# 1.net
KiCad netlist of a schematic drawn in Altium Designer
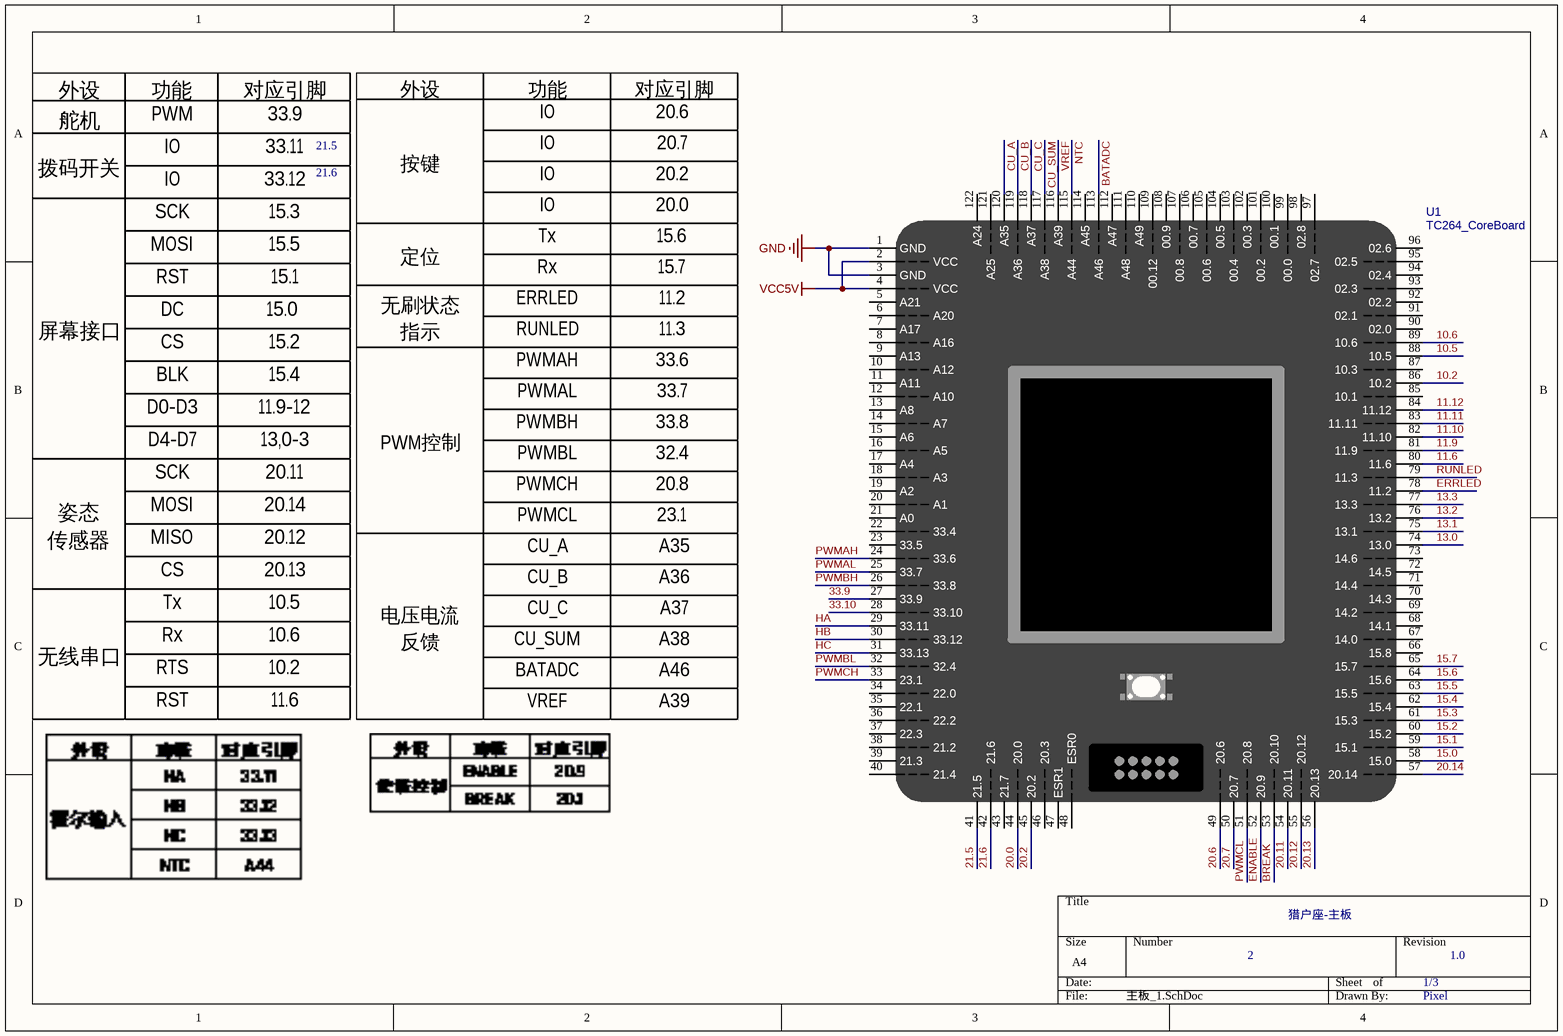
[diagram p0: 主板_1.SchDoc]

(export (version "E")
  (design (tool "Eeschema 10.0.6"))
  (components
    (comp (ref "U1")
      (value "TC264_CoreBoard")
      (footprint "TC264_CoreBoard")
      (description "逐飞科技TC264核心板")
      (libsource (lib "TC264_主板_V2.6") (part "TC264_CoreBoard"))
    )
  )
  (nets
    (net (code "1") (name "/10.2") (class "Default")
      (node (ref "U1") (pin "86") (pinfunction "10.2_86") (pintype "passive"))
    )
    (net (code "2") (name "/10.5") (class "Default")
      (node (ref "U1") (pin "88") (pinfunction "10.5_88") (pintype "passive"))
    )
    (net (code "3") (name "/10.6") (class "Default")
      (node (ref "U1") (pin "89") (pinfunction "10.6_89") (pintype "passive"))
    )
    (net (code "4") (name "/11.6") (class "Default")
      (node (ref "U1") (pin "80") (pinfunction "11.6_80") (pintype "passive"))
    )
    (net (code "5") (name "/11.9") (class "Default")
      (node (ref "U1") (pin "81") (pinfunction "11.9_81") (pintype "passive"))
    )
    (net (code "6") (name "/11.10") (class "Default")
      (node (ref "U1") (pin "82") (pinfunction "11.10_82") (pintype "passive"))
    )
    (net (code "7") (name "/11.11") (class "Default")
      (node (ref "U1") (pin "83") (pinfunction "11.11_83") (pintype "passive"))
    )
    (net (code "8") (name "/11.12") (class "Default")
      (node (ref "U1") (pin "84") (pinfunction "11.12_84") (pintype "passive"))
    )
    (net (code "9") (name "/13.0") (class "Default")
      (node (ref "U1") (pin "74") (pinfunction "13.0_74") (pintype "passive"))
    )
    (net (code "10") (name "/13.1") (class "Default")
      (node (ref "U1") (pin "75") (pinfunction "13.1_75") (pintype "passive"))
    )
    (net (code "11") (name "/13.2") (class "Default")
      (node (ref "U1") (pin "76") (pinfunction "13.2_76") (pintype "passive"))
    )
    (net (code "12") (name "/13.3") (class "Default")
      (node (ref "U1") (pin "77") (pinfunction "13.3_77") (pintype "passive"))
    )
    (net (code "13") (name "/15.0") (class "Default")
      (node (ref "U1") (pin "58") (pinfunction "15.0_58") (pintype "passive"))
    )
    (net (code "14") (name "/15.1") (class "Default")
      (node (ref "U1") (pin "59") (pinfunction "15.1_59") (pintype "passive"))
    )
    (net (code "15") (name "/15.2") (class "Default")
      (node (ref "U1") (pin "60") (pinfunction "15.2_60") (pintype "passive"))
    )
    (net (code "16") (name "/15.3") (class "Default")
      (node (ref "U1") (pin "61") (pinfunction "15.3_61") (pintype "passive"))
    )
    (net (code "17") (name "/15.4") (class "Default")
      (node (ref "U1") (pin "62") (pinfunction "15.4_62") (pintype "passive"))
    )
    (net (code "18") (name "/15.5") (class "Default")
      (node (ref "U1") (pin "63") (pinfunction "15.5_63") (pintype "passive"))
    )
    (net (code "19") (name "/15.6") (class "Default")
      (node (ref "U1") (pin "64") (pinfunction "15.6_64") (pintype "passive"))
    )
    (net (code "20") (name "/15.7") (class "Default")
      (node (ref "U1") (pin "65") (pinfunction "15.7_65") (pintype "passive"))
    )
    (net (code "21") (name "/20.0") (class "Default")
      (node (ref "U1") (pin "44") (pinfunction "20.0_44") (pintype "passive"))
    )
    (net (code "22") (name "/20.2") (class "Default")
      (node (ref "U1") (pin "45") (pinfunction "20.2_45") (pintype "passive"))
    )
    (net (code "23") (name "/20.6") (class "Default")
      (node (ref "U1") (pin "49") (pinfunction "20.6_49") (pintype "passive"))
    )
    (net (code "24") (name "/20.7") (class "Default")
      (node (ref "U1") (pin "50") (pinfunction "20.7_50") (pintype "passive"))
    )
    (net (code "25") (name "/20.11") (class "Default")
      (node (ref "U1") (pin "54") (pinfunction "20.11_54") (pintype "passive"))
    )
    (net (code "26") (name "/20.12") (class "Default")
      (node (ref "U1") (pin "55") (pinfunction "20.12_55") (pintype "passive"))
    )
    (net (code "27") (name "/20.13") (class "Default")
      (node (ref "U1") (pin "56") (pinfunction "20.13_56") (pintype "passive"))
    )
    (net (code "28") (name "/20.14") (class "Default")
      (node (ref "U1") (pin "57") (pinfunction "20.14_57") (pintype "passive"))
    )
    (net (code "29") (name "/21.5") (class "Default")
      (node (ref "U1") (pin "41") (pinfunction "21.5_41") (pintype "passive"))
    )
    (net (code "30") (name "/21.6") (class "Default")
      (node (ref "U1") (pin "42") (pinfunction "21.6_42") (pintype "passive"))
    )
    (net (code "31") (name "/33.9") (class "Default")
      (node (ref "U1") (pin "27") (pinfunction "33.9_27") (pintype "passive"))
    )
    (net (code "32") (name "/33.10") (class "Default")
      (node (ref "U1") (pin "28") (pinfunction "33.10_28") (pintype "passive"))
    )
    (net (code "33") (name "/BATADC") (class "Default")
      (node (ref "U1") (pin "113") (pinfunction "A46_113") (pintype "passive"))
    )
    (net (code "34") (name "/BREAK") (class "Default")
      (node (ref "U1") (pin "53") (pinfunction "20.10_53") (pintype "passive"))
    )
    (net (code "35") (name "/CU_A") (class "Default")
      (node (ref "U1") (pin "120") (pinfunction "A35_120") (pintype "passive"))
    )
    (net (code "36") (name "/CU_B") (class "Default")
      (node (ref "U1") (pin "119") (pinfunction "A36_119") (pintype "passive"))
    )
    (net (code "37") (name "/CU_C") (class "Default")
      (node (ref "U1") (pin "118") (pinfunction "A37_118") (pintype "passive"))
    )
    (net (code "38") (name "/CU_SUM") (class "Default")
      (node (ref "U1") (pin "117") (pinfunction "A38_117") (pintype "passive"))
    )
    (net (code "39") (name "/ENABLE") (class "Default")
      (node (ref "U1") (pin "52") (pinfunction "20.9_52") (pintype "passive"))
    )
    (net (code "40") (name "/ERRLED") (class "Default")
      (node (ref "U1") (pin "78") (pinfunction "11.2_78") (pintype "passive"))
    )
    (net (code "41") (name "/HA") (class "Default")
      (node (ref "U1") (pin "29") (pinfunction "33.11_29") (pintype "passive"))
    )
    (net (code "42") (name "/HB") (class "Default")
      (node (ref "U1") (pin "30") (pinfunction "33.12_30") (pintype "passive"))
    )
    (net (code "43") (name "/HC") (class "Default")
      (node (ref "U1") (pin "31") (pinfunction "33.13_31") (pintype "passive"))
    )
    (net (code "44") (name "/NTC") (class "Default")
      (node (ref "U1") (pin "115") (pinfunction "A44_115") (pintype "passive"))
    )
    (net (code "45") (name "/PWMAH") (class "Default")
      (node (ref "U1") (pin "24") (pinfunction "33.6_24") (pintype "passive"))
    )
    (net (code "46") (name "/PWMAL") (class "Default")
      (node (ref "U1") (pin "25") (pinfunction "33.7_25") (pintype "passive"))
    )
    (net (code "47") (name "/PWMBH") (class "Default")
      (node (ref "U1") (pin "26") (pinfunction "33.8_26") (pintype "passive"))
    )
    (net (code "48") (name "/PWMBL") (class "Default")
      (node (ref "U1") (pin "32") (pinfunction "32.4_32") (pintype "passive"))
    )
    (net (code "49") (name "/PWMCH") (class "Default")
      (node (ref "U1") (pin "33") (pinfunction "23.1_33") (pintype "passive"))
    )
    (net (code "50") (name "/PWMCL") (class "Default")
      (node (ref "U1") (pin "51") (pinfunction "20.8_51") (pintype "passive"))
    )
    (net (code "51") (name "/RUNLED") (class "Default")
      (node (ref "U1") (pin "79") (pinfunction "11.3_79") (pintype "passive"))
    )
    (net (code "52") (name "/VREF") (class "Default")
      (node (ref "U1") (pin "116") (pinfunction "A39_116") (pintype "passive"))
    )
    (net (code "53") (name "GND") (class "Default")
      (node (ref "U1") (pin "1") (pinfunction "GND_1") (pintype "passive"))
      (node (ref "U1") (pin "3") (pinfunction "GND_3") (pintype "passive"))
    )
    (net (code "54") (name "VCC5V") (class "Default")
      (node (ref "U1") (pin "2") (pinfunction "VCC_2") (pintype "passive"))
      (node (ref "U1") (pin "4") (pinfunction "VCC_4") (pintype "passive"))
    )
    (net (code "55") (name "unconnected-(U1-00.0-Pad99)") (class "Default")
      (node (ref "U1") (pin "99") (pinfunction "00.0_99") (pintype "passive"))
    )
    (net (code "56") (name "unconnected-(U1-00.1-Pad100)") (class "Default")
      (node (ref "U1") (pin "100") (pinfunction "00.1_100") (pintype "passive"))
    )
    (net (code "57") (name "unconnected-(U1-00.2-Pad101)") (class "Default")
      (node (ref "U1") (pin "101") (pinfunction "00.2_101") (pintype "passive"))
    )
    (net (code "58") (name "unconnected-(U1-00.3-Pad102)") (class "Default")
      (node (ref "U1") (pin "102") (pinfunction "00.3_102") (pintype "passive"))
    )
    (net (code "59") (name "unconnected-(U1-00.4-Pad103)") (class "Default")
      (node (ref "U1") (pin "103") (pinfunction "00.4_103") (pintype "passive"))
    )
    (net (code "60") (name "unconnected-(U1-00.5-Pad104)") (class "Default")
      (node (ref "U1") (pin "104") (pinfunction "00.5_104") (pintype "passive"))
    )
    (net (code "61") (name "unconnected-(U1-00.6-Pad105)") (class "Default")
      (node (ref "U1") (pin "105") (pinfunction "00.6_105") (pintype "passive"))
    )
    (net (code "62") (name "unconnected-(U1-00.7-Pad106)") (class "Default")
      (node (ref "U1") (pin "106") (pinfunction "00.7_106") (pintype "passive"))
    )
    (net (code "63") (name "unconnected-(U1-00.8-Pad107)") (class "Default")
      (node (ref "U1") (pin "107") (pinfunction "00.8_107") (pintype "passive"))
    )
    (net (code "64") (name "unconnected-(U1-00.9-Pad108)") (class "Default")
      (node (ref "U1") (pin "108") (pinfunction "00.9_108") (pintype "passive"))
    )
    (net (code "65") (name "unconnected-(U1-00.12-Pad109)") (class "Default")
      (node (ref "U1") (pin "109") (pinfunction "00.12_109") (pintype "passive"))
    )
    (net (code "66") (name "unconnected-(U1-02.0-Pad90)") (class "Default")
      (node (ref "U1") (pin "90") (pinfunction "02.0_90") (pintype "passive"))
    )
    (net (code "67") (name "unconnected-(U1-02.1-Pad91)") (class "Default")
      (node (ref "U1") (pin "91") (pinfunction "02.1_91") (pintype "passive"))
    )
    (net (code "68") (name "unconnected-(U1-02.2-Pad92)") (class "Default")
      (node (ref "U1") (pin "92") (pinfunction "02.2_92") (pintype "passive"))
    )
    (net (code "69") (name "unconnected-(U1-02.3-Pad93)") (class "Default")
      (node (ref "U1") (pin "93") (pinfunction "02.3_93") (pintype "passive"))
    )
    (net (code "70") (name "unconnected-(U1-02.4-Pad94)") (class "Default")
      (node (ref "U1") (pin "94") (pinfunction "02.4_94") (pintype "passive"))
    )
    (net (code "71") (name "unconnected-(U1-02.5-Pad95)") (class "Default")
      (node (ref "U1") (pin "95") (pinfunction "02.5_95") (pintype "passive"))
    )
    (net (code "72") (name "unconnected-(U1-02.6-Pad96)") (class "Default")
      (node (ref "U1") (pin "96") (pinfunction "02.6_96") (pintype "passive"))
    )
    (net (code "73") (name "unconnected-(U1-02.7-Pad97)") (class "Default")
      (node (ref "U1") (pin "97") (pinfunction "02.7_97") (pintype "passive"))
    )
    (net (code "74") (name "unconnected-(U1-02.8-Pad98)") (class "Default")
      (node (ref "U1") (pin "98") (pinfunction "02.8_98") (pintype "passive"))
    )
    (net (code "75") (name "unconnected-(U1-10.1-Pad85)") (class "Default")
      (node (ref "U1") (pin "85") (pinfunction "10.1_85") (pintype "passive"))
    )
    (net (code "76") (name "unconnected-(U1-10.3-Pad87)") (class "Default")
      (node (ref "U1") (pin "87") (pinfunction "10.3_87") (pintype "passive"))
    )
    (net (code "77") (name "unconnected-(U1-14.0-Pad67)") (class "Default")
      (node (ref "U1") (pin "67") (pinfunction "14.0_67") (pintype "passive"))
    )
    (net (code "78") (name "unconnected-(U1-14.1-Pad68)") (class "Default")
      (node (ref "U1") (pin "68") (pinfunction "14.1_68") (pintype "passive"))
    )
    (net (code "79") (name "unconnected-(U1-14.2-Pad69)") (class "Default")
      (node (ref "U1") (pin "69") (pinfunction "14.2_69") (pintype "passive"))
    )
    (net (code "80") (name "unconnected-(U1-14.3-Pad70)") (class "Default")
      (node (ref "U1") (pin "70") (pinfunction "14.3_70") (pintype "passive"))
    )
    (net (code "81") (name "unconnected-(U1-14.4-Pad71)") (class "Default")
      (node (ref "U1") (pin "71") (pinfunction "14.4_71") (pintype "passive"))
    )
    (net (code "82") (name "unconnected-(U1-14.5-Pad72)") (class "Default")
      (node (ref "U1") (pin "72") (pinfunction "14.5_72") (pintype "passive"))
    )
    (net (code "83") (name "unconnected-(U1-14.6-Pad73)") (class "Default")
      (node (ref "U1") (pin "73") (pinfunction "14.6_73") (pintype "passive"))
    )
    (net (code "84") (name "unconnected-(U1-15.8-Pad66)") (class "Default")
      (node (ref "U1") (pin "66") (pinfunction "15.8_66") (pintype "passive"))
    )
    (net (code "85") (name "unconnected-(U1-20.3-Pad46)") (class "Default")
      (node (ref "U1") (pin "46") (pinfunction "20.3_46") (pintype "passive"))
    )
    (net (code "86") (name "unconnected-(U1-21.2-Pad38)") (class "Default")
      (node (ref "U1") (pin "38") (pinfunction "21.2_38") (pintype "passive"))
    )
    (net (code "87") (name "unconnected-(U1-21.3-Pad39)") (class "Default")
      (node (ref "U1") (pin "39") (pinfunction "21.3_39") (pintype "passive"))
    )
    (net (code "88") (name "unconnected-(U1-21.4-Pad40)") (class "Default")
      (node (ref "U1") (pin "40") (pinfunction "21.4_40") (pintype "passive"))
    )
    (net (code "89") (name "unconnected-(U1-21.7-Pad43)") (class "Default")
      (node (ref "U1") (pin "43") (pinfunction "21.7_43") (pintype "passive"))
    )
    (net (code "90") (name "unconnected-(U1-22.0-Pad34)") (class "Default")
      (node (ref "U1") (pin "34") (pinfunction "22.0_34") (pintype "passive"))
    )
    (net (code "91") (name "unconnected-(U1-22.1-Pad35)") (class "Default")
      (node (ref "U1") (pin "35") (pinfunction "22.1_35") (pintype "passive"))
    )
    (net (code "92") (name "unconnected-(U1-22.2-Pad36)") (class "Default")
      (node (ref "U1") (pin "36") (pinfunction "22.2_36") (pintype "passive"))
    )
    (net (code "93") (name "unconnected-(U1-22.3-Pad37)") (class "Default")
      (node (ref "U1") (pin "37") (pinfunction "22.3_37") (pintype "passive"))
    )
    (net (code "94") (name "unconnected-(U1-33.4-Pad22)") (class "Default")
      (node (ref "U1") (pin "22") (pinfunction "33.4_22") (pintype "passive"))
    )
    (net (code "95") (name "unconnected-(U1-33.5-Pad23)") (class "Default")
      (node (ref "U1") (pin "23") (pinfunction "33.5_23") (pintype "passive"))
    )
    (net (code "96") (name "unconnected-(U1-A0-Pad21)") (class "Default")
      (node (ref "U1") (pin "21") (pinfunction "A0_21") (pintype "passive"))
    )
    (net (code "97") (name "unconnected-(U1-A1-Pad20)") (class "Default")
      (node (ref "U1") (pin "20") (pinfunction "A1_20") (pintype "passive"))
    )
    (net (code "98") (name "unconnected-(U1-A2-Pad19)") (class "Default")
      (node (ref "U1") (pin "19") (pinfunction "A2_19") (pintype "passive"))
    )
    (net (code "99") (name "unconnected-(U1-A3-Pad18)") (class "Default")
      (node (ref "U1") (pin "18") (pinfunction "A3_18") (pintype "passive"))
    )
    (net (code "100") (name "unconnected-(U1-A4-Pad17)") (class "Default")
      (node (ref "U1") (pin "17") (pinfunction "A4_17") (pintype "passive"))
    )
    (net (code "101") (name "unconnected-(U1-A5-Pad16)") (class "Default")
      (node (ref "U1") (pin "16") (pinfunction "A5_16") (pintype "passive"))
    )
    (net (code "102") (name "unconnected-(U1-A6-Pad15)") (class "Default")
      (node (ref "U1") (pin "15") (pinfunction "A6_15") (pintype "passive"))
    )
    (net (code "103") (name "unconnected-(U1-A7-Pad14)") (class "Default")
      (node (ref "U1") (pin "14") (pinfunction "A7_14") (pintype "passive"))
    )
    (net (code "104") (name "unconnected-(U1-A8-Pad13)") (class "Default")
      (node (ref "U1") (pin "13") (pinfunction "A8_13") (pintype "passive"))
    )
    (net (code "105") (name "unconnected-(U1-A10-Pad12)") (class "Default")
      (node (ref "U1") (pin "12") (pinfunction "A10_12") (pintype "passive"))
    )
    (net (code "106") (name "unconnected-(U1-A11-Pad11)") (class "Default")
      (node (ref "U1") (pin "11") (pinfunction "A11_11") (pintype "passive"))
    )
    (net (code "107") (name "unconnected-(U1-A12-Pad10)") (class "Default")
      (node (ref "U1") (pin "10") (pinfunction "A12_10") (pintype "passive"))
    )
    (net (code "108") (name "unconnected-(U1-A13-Pad9)") (class "Default")
      (node (ref "U1") (pin "9") (pinfunction "A13_9") (pintype "passive"))
    )
    (net (code "109") (name "unconnected-(U1-A16-Pad8)") (class "Default")
      (node (ref "U1") (pin "8") (pinfunction "A16_8") (pintype "passive"))
    )
    (net (code "110") (name "unconnected-(U1-A17-Pad7)") (class "Default")
      (node (ref "U1") (pin "7") (pinfunction "A17_7") (pintype "passive"))
    )
    (net (code "111") (name "unconnected-(U1-A20-Pad6)") (class "Default")
      (node (ref "U1") (pin "6") (pinfunction "A20_6") (pintype "passive"))
    )
    (net (code "112") (name "unconnected-(U1-A21-Pad5)") (class "Default")
      (node (ref "U1") (pin "5") (pinfunction "A21_5") (pintype "passive"))
    )
    (net (code "113") (name "unconnected-(U1-A24-Pad122)") (class "Default")
      (node (ref "U1") (pin "122") (pinfunction "A24_122") (pintype "passive"))
    )
    (net (code "114") (name "unconnected-(U1-A25-Pad121)") (class "Default")
      (node (ref "U1") (pin "121") (pinfunction "A25_121") (pintype "passive"))
    )
    (net (code "115") (name "unconnected-(U1-A45-Pad114)") (class "Default")
      (node (ref "U1") (pin "114") (pinfunction "A45_114") (pintype "passive"))
    )
    (net (code "116") (name "unconnected-(U1-A47-Pad112)") (class "Default")
      (node (ref "U1") (pin "112") (pinfunction "A47_112") (pintype "passive"))
    )
    (net (code "117") (name "unconnected-(U1-A48-Pad111)") (class "Default")
      (node (ref "U1") (pin "111") (pinfunction "A48_111") (pintype "passive"))
    )
    (net (code "118") (name "unconnected-(U1-A49-Pad110)") (class "Default")
      (node (ref "U1") (pin "110") (pinfunction "A49_110") (pintype "passive"))
    )
    (net (code "119") (name "unconnected-(U1-ESR0-Pad48)") (class "Default")
      (node (ref "U1") (pin "48") (pinfunction "ESR0_48") (pintype "passive"))
    )
    (net (code "120") (name "unconnected-(U1-ESR1-Pad47)") (class "Default")
      (node (ref "U1") (pin "47") (pinfunction "ESR1_47") (pintype "passive"))
    )
  )
)
